# Sheet2.net
KiCad netlist of a schematic drawn in Altium Designer
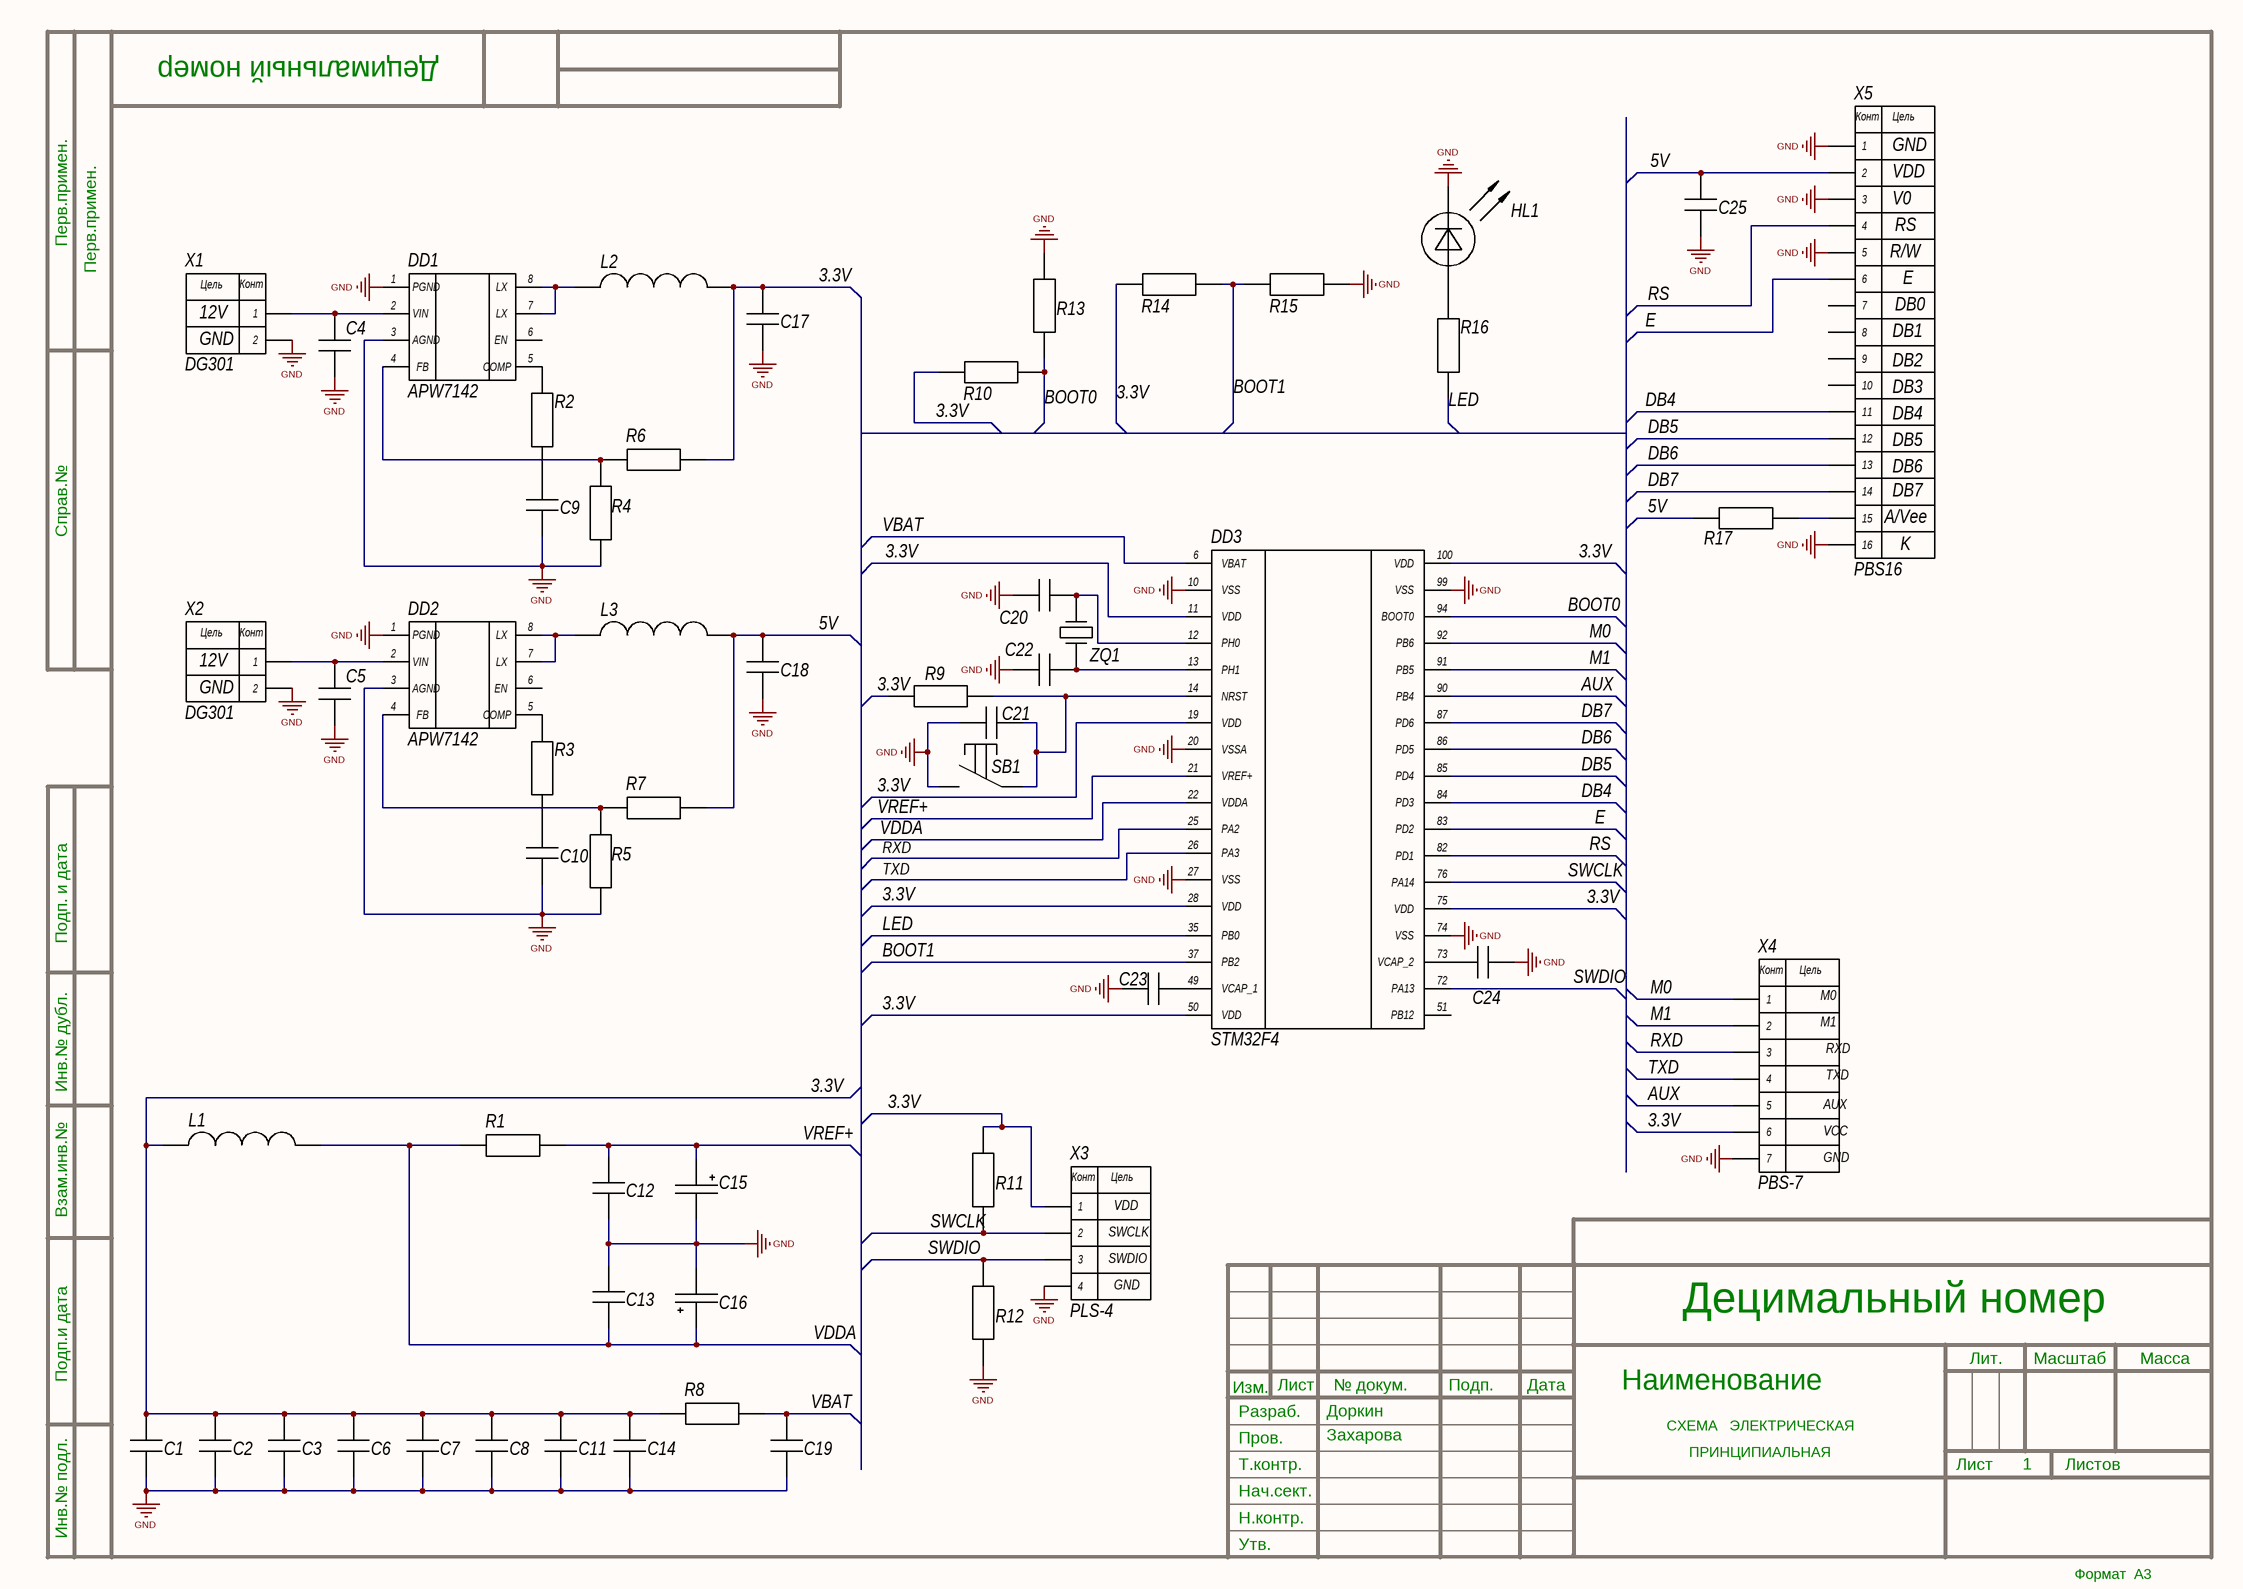
[diagram p0: Sheet2.SchDoc]

(export (version "E")
  (design (tool "Eeschema 10.0.6"))
  (components
    (comp (ref "C1") (value "100nF") (footprint "R1206") (libsource (lib "Schlib1") (part "C")))
    (comp (ref "C2") (value "C") (footprint "R1206") (libsource (lib "Schlib1") (part "C")))
    (comp (ref "C3") (value "C") (footprint "R1206") (libsource (lib "Schlib1") (part "C")))
    (comp (ref "C4") (value "2.2uF") (footprint "R1206") (libsource (lib "Schlib1") (part "C")))
    (comp (ref "C5") (value "2.2uF") (footprint "R1206") (libsource (lib "Schlib1") (part "C")))
    (comp (ref "C6") (value "C") (footprint "R1206") (libsource (lib "Schlib1") (part "C")))
    (comp (ref "C7") (value "C") (footprint "R1206") (libsource (lib "Schlib1") (part "C")))
    (comp (ref "C8") (value "C") (footprint "R1206") (libsource (lib "Schlib1") (part "C")))
    (comp (ref "C9") (value "1.5nF") (footprint "R1206") (libsource (lib "Schlib1") (part "C")))
    (comp (ref "C10") (value "1.5nF") (footprint "R1206") (libsource (lib "Schlib1") (part "C")))
    (comp (ref "C11") (value "C") (footprint "R1206") (libsource (lib "Schlib1") (part "C")))
    (comp (ref "C12") (value "1uF") (footprint "R1206") (libsource (lib "Schlib1") (part "C")))
    (comp (ref "C13") (value "1uF") (footprint "R1206") (libsource (lib "Schlib1") (part "C")))
    (comp (ref "C14") (value "C") (footprint "R1206") (libsource (lib "Schlib1") (part "C")))
    (comp (ref "C15") (value "100nF") (footprint "Rc3216") (libsource (lib "Schlib1") (part "C+")))
    (comp (ref "C16") (value "100nF") (footprint "Rc3216") (libsource (lib "Schlib1") (part "C+")))
    (comp (ref "C17") (value "22uF") (footprint "R1206") (libsource (lib "Schlib1") (part "C")))
    (comp (ref "C18") (value "22uF") (footprint "R1206") (libsource (lib "Schlib1") (part "C")))
    (comp (ref "C19") (value "1uF") (footprint "R1206") (libsource (lib "Schlib1") (part "C")))
    (comp (ref "C20") (value "20pF") (footprint "R1206") (libsource (lib "Schlib1") (part "C")))
    (comp (ref "C21") (value "100nF") (footprint "R1206") (libsource (lib "Schlib1") (part "C")))
    (comp (ref "C22") (value "20pF") (footprint "R1206") (libsource (lib "Schlib1") (part "C")))
    (comp (ref "C23") (value "2.2uF") (footprint "R1206") (libsource (lib "Schlib1") (part "C")))
    (comp (ref "C24") (value "2.2uF") (footprint "R1206") (libsource (lib "Schlib1") (part "C")))
    (comp (ref "C25") (value "100nF") (footprint "R1206") (libsource (lib "Schlib1") (part "C")))
    (comp (ref "DD1") (value "APW7142") (footprint "APW7142") (libsource (lib "Schlib1") (part "APW7142")))
    (comp (ref "DD2") (value "APW7142") (footprint "APW7142") (libsource (lib "Schlib1") (part "APW7142")))
    (comp (ref "DD3") (value "STM32F4") (footprint "STM32F4xx") (libsource (lib "Schlib1") (part "STM32F4")))
    (comp (ref "HL1") (value "Led") (footprint "LED") (libsource (lib "Schlib1") (part "Led")))
    (comp (ref "L1") (value "4.7uH") (footprint "R1206") (libsource (lib "Schlib1") (part "L")))
    (comp (ref "L2") (value "4.7uH") (footprint "R1206") (libsource (lib "Schlib1") (part "L")))
    (comp (ref "L3") (value "6.8uH") (footprint "R1206") (libsource (lib "Schlib1") (part "L")))
    (comp (ref "R1") (value "47") (footprint "R1206") (libsource (lib "Schlib1") (part "Res")))
    (comp (ref "R2") (value "10k") (footprint "R1206") (libsource (lib "Schlib1") (part "Res")))
    (comp (ref "R3") (value "10k") (footprint "R1206") (libsource (lib "Schlib1") (part "Res")))
    (comp (ref "R4") (value "15k") (footprint "R1206") (libsource (lib "Schlib1") (part "Res")))
    (comp (ref "R5") (value "12k") (footprint "R1206") (libsource (lib "Schlib1") (part "Res")))
    (comp (ref "R6") (value "46.9k") (footprint "R1206") (libsource (lib "Schlib1") (part "Res")))
    (comp (ref "R7") (value "63k") (footprint "R1206") (libsource (lib "Schlib1") (part "Res")))
    (comp (ref "R8") (value "10k") (footprint "R1206") (libsource (lib "Schlib1") (part "Res")))
    (comp (ref "R9") (value "100k") (footprint "R1206") (libsource (lib "Schlib1") (part "Res")))
    (comp (ref "R10") (value "100k") (footprint "R1206") (libsource (lib "Schlib1") (part "Res")))
    (comp (ref "R11") (value "10k") (footprint "R1206") (libsource (lib "Schlib1") (part "Res")))
    (comp (ref "R12") (value "10k") (footprint "R1206") (libsource (lib "Schlib1") (part "Res")))
    (comp (ref "R13") (value "510") (footprint "R1206") (libsource (lib "") (part "Res_1")))
    (comp (ref "R14") (value "10k") (footprint "R1206") (libsource (lib "Schlib1") (part "Res")))
    (comp (ref "R15") (value "510") (footprint "R1206") (libsource (lib "") (part "Res_1")))
    (comp (ref "R16") (value "Res") (footprint "R1206") (libsource (lib "Schlib1") (part "Res")))
    (comp (ref "R17") (value "100") (footprint "R1206") (libsource (lib "Schlib1") (part "Res")))
    (comp (ref "SB1") (value "BUTTON") (footprint "RESET_BUTTON") (libsource (lib "Schlib1") (part "BUTTON")))
    (comp (ref "X1") (value "DG301") (footprint "DG301") (libsource (lib "Schlib1") (part "DG301")))
    (comp (ref "X2") (value "DG301") (footprint "DG301") (libsource (lib "Schlib1") (part "DG301")))
    (comp (ref "X3") (value "PLS-4") (footprint "PLS4") (libsource (lib "Schlib1") (part "PLS-4")))
    (comp (ref "X4") (value "PBS-7") (footprint "PBS7") (libsource (lib "Schlib1") (part "PBS-7")))
    (comp (ref "X5") (value "PBS16") (footprint "PBS16") (libsource (lib "Schlib1") (part "Wh1602C")))
    (comp (ref "ZQ1") (value "KR") (footprint "HC-49SM") (libsource (lib "Schlib1") (part "KR")))
  )
  (nets
    (net (code "1") (name "/3.3V") (class "Default")
      (node (ref "C1") (pin "2") (pinfunction "2_2") (pintype "passive"))
      (node (ref "C11") (pin "2") (pinfunction "2_2") (pintype "passive"))
      (node (ref "C14") (pin "2") (pinfunction "2_2") (pintype "passive"))
      (node (ref "C17") (pin "1") (pinfunction "1_1") (pintype "passive"))
      (node (ref "C2") (pin "2") (pinfunction "2_2") (pintype "passive"))
      (node (ref "C3") (pin "2") (pinfunction "2_2") (pintype "passive"))
      (node (ref "C6") (pin "2") (pinfunction "2_2") (pintype "passive"))
      (node (ref "C7") (pin "2") (pinfunction "2_2") (pintype "passive"))
      (node (ref "C8") (pin "2") (pinfunction "2_2") (pintype "passive"))
      (node (ref "DD3") (pin "100") (pinfunction "VDD_100") (pintype "passive"))
      (node (ref "DD3") (pin "11") (pinfunction "VDD_11") (pintype "passive"))
      (node (ref "DD3") (pin "19") (pinfunction "VDD_19") (pintype "passive"))
      (node (ref "DD3") (pin "28") (pinfunction "VDD_28") (pintype "passive"))
      (node (ref "DD3") (pin "50") (pinfunction "VDD_50") (pintype "passive"))
      (node (ref "DD3") (pin "75") (pinfunction "VDD_75") (pintype "passive"))
      (node (ref "L1") (pin "1") (pinfunction "1_1") (pintype "passive"))
      (node (ref "L2") (pin "2") (pinfunction "2_2") (pintype "passive"))
      (node (ref "R10") (pin "2") (pinfunction "2_2") (pintype "passive"))
      (node (ref "R11") (pin "2") (pinfunction "2_2") (pintype "passive"))
      (node (ref "R14") (pin "1") (pinfunction "1_1") (pintype "passive"))
      (node (ref "R6") (pin "2") (pinfunction "2_2") (pintype "passive"))
      (node (ref "R8") (pin "1") (pinfunction "1_1") (pintype "passive"))
      (node (ref "R9") (pin "1") (pinfunction "1_1") (pintype "passive"))
      (node (ref "X3") (pin "1") (pinfunction "1_1") (pintype "passive"))
      (node (ref "X4") (pin "6") (pinfunction "6_6") (pintype "passive"))
    )
    (net (code "2") (name "/5V") (class "Default")
      (node (ref "C18") (pin "1") (pinfunction "1_1") (pintype "passive"))
      (node (ref "C25") (pin "2") (pinfunction "2_2") (pintype "passive"))
      (node (ref "L3") (pin "2") (pinfunction "2_2") (pintype "passive"))
      (node (ref "R17") (pin "1") (pinfunction "1_1") (pintype "passive"))
      (node (ref "R7") (pin "2") (pinfunction "2_2") (pintype "passive"))
      (node (ref "X5") (pin "2") (pinfunction "2_2") (pintype "passive"))
    )
    (net (code "3") (name "/AUX") (class "Default")
      (node (ref "DD3") (pin "90") (pinfunction "PB4_90") (pintype "passive"))
      (node (ref "X4") (pin "5") (pinfunction "5_5") (pintype "passive"))
    )
    (net (code "4") (name "/BOOT0") (class "Default")
      (node (ref "DD3") (pin "94") (pinfunction "BOOT0_94") (pintype "passive"))
      (node (ref "R10") (pin "1") (pinfunction "1_1") (pintype "passive"))
      (node (ref "R13") (pin "1") (pinfunction "1_1") (pintype "passive"))
    )
    (net (code "5") (name "/BOOT1") (class "Default")
      (node (ref "DD3") (pin "37") (pinfunction "PB2_37") (pintype "passive"))
      (node (ref "R14") (pin "2") (pinfunction "2_2") (pintype "passive"))
      (node (ref "R15") (pin "1") (pinfunction "1_1") (pintype "passive"))
    )
    (net (code "6") (name "/DB4") (class "Default")
      (node (ref "DD3") (pin "84") (pinfunction "PD3_84") (pintype "passive"))
      (node (ref "X5") (pin "11") (pinfunction "11_11") (pintype "passive"))
    )
    (net (code "7") (name "/DB5") (class "Default")
      (node (ref "DD3") (pin "85") (pinfunction "PD4_85") (pintype "passive"))
      (node (ref "X5") (pin "12") (pinfunction "12_12") (pintype "passive"))
    )
    (net (code "8") (name "/DB6") (class "Default")
      (node (ref "DD3") (pin "86") (pinfunction "PD5_86") (pintype "passive"))
      (node (ref "X5") (pin "13") (pinfunction "13_13") (pintype "passive"))
    )
    (net (code "9") (name "/DB7") (class "Default")
      (node (ref "DD3") (pin "87") (pinfunction "PD6_87") (pintype "passive"))
      (node (ref "X5") (pin "14") (pinfunction "14_14") (pintype "passive"))
    )
    (net (code "10") (name "/E") (class "Default")
      (node (ref "DD3") (pin "83") (pinfunction "PD2_83") (pintype "passive"))
      (node (ref "X5") (pin "18") (pinfunction "6_18") (pintype "passive"))
    )
    (net (code "11") (name "/LED") (class "Default")
      (node (ref "DD3") (pin "35") (pinfunction "PB0_35") (pintype "passive"))
      (node (ref "R16") (pin "1") (pinfunction "1_1") (pintype "passive"))
    )
    (net (code "12") (name "/M0") (class "Default")
      (node (ref "DD3") (pin "92") (pinfunction "PB6_92") (pintype "passive"))
      (node (ref "X4") (pin "1") (pinfunction "1_1") (pintype "passive"))
    )
    (net (code "13") (name "/M1") (class "Default")
      (node (ref "DD3") (pin "91") (pinfunction "PB5_91") (pintype "passive"))
      (node (ref "X4") (pin "2") (pinfunction "2_2") (pintype "passive"))
    )
    (net (code "14") (name "/RS") (class "Default")
      (node (ref "DD3") (pin "82") (pinfunction "PD1_82") (pintype "passive"))
      (node (ref "X5") (pin "4") (pinfunction "4_4") (pintype "passive"))
    )
    (net (code "15") (name "/RXD") (class "Default")
      (node (ref "DD3") (pin "25") (pinfunction "PA2_25") (pintype "passive"))
      (node (ref "X4") (pin "3") (pinfunction "3_3") (pintype "passive"))
    )
    (net (code "16") (name "/SWCLK") (class "Default")
      (node (ref "DD3") (pin "76") (pinfunction "PA14_76") (pintype "passive"))
      (node (ref "R11") (pin "1") (pinfunction "1_1") (pintype "passive"))
      (node (ref "X3") (pin "2") (pinfunction "2_2") (pintype "passive"))
    )
    (net (code "17") (name "/SWDIO") (class "Default")
      (node (ref "DD3") (pin "72") (pinfunction "PA13_72") (pintype "passive"))
      (node (ref "R12") (pin "2") (pinfunction "2_2") (pintype "passive"))
      (node (ref "X3") (pin "3") (pinfunction "3_3") (pintype "passive"))
    )
    (net (code "18") (name "/TXD") (class "Default")
      (node (ref "DD3") (pin "26") (pinfunction "PA3_26") (pintype "passive"))
      (node (ref "X4") (pin "4") (pinfunction "4_4") (pintype "passive"))
    )
    (net (code "19") (name "/VBAT") (class "Default")
      (node (ref "C19") (pin "2") (pinfunction "2_2") (pintype "passive"))
      (node (ref "DD3") (pin "6") (pinfunction "VBAT_6") (pintype "passive"))
      (node (ref "R8") (pin "2") (pinfunction "2_2") (pintype "passive"))
    )
    (net (code "20") (name "/VDDA") (class "Default")
      (node (ref "C13") (pin "1") (pinfunction "1_1") (pintype "passive"))
      (node (ref "C16") (pin "1") (pinfunction "1_1") (pintype "passive"))
      (node (ref "DD3") (pin "22") (pinfunction "VDDA_22") (pintype "passive"))
      (node (ref "L1") (pin "2") (pinfunction "2_2") (pintype "passive"))
      (node (ref "R1") (pin "1") (pinfunction "1_1") (pintype "passive"))
    )
    (net (code "21") (name "/VREF+") (class "Default")
      (node (ref "C12") (pin "2") (pinfunction "2_2") (pintype "passive"))
      (node (ref "C15") (pin "1") (pinfunction "1_1") (pintype "passive"))
      (node (ref "DD3") (pin "21") (pinfunction "VREF+_21") (pintype "passive"))
      (node (ref "R1") (pin "2") (pinfunction "2_2") (pintype "passive"))
    )
    (net (code "22") (name "GND") (class "Default")
      (node (ref "C1") (pin "1") (pinfunction "1_1") (pintype "passive"))
      (node (ref "C10") (pin "1") (pinfunction "1_1") (pintype "passive"))
      (node (ref "C11") (pin "1") (pinfunction "1_1") (pintype "passive"))
      (node (ref "C12") (pin "1") (pinfunction "1_1") (pintype "passive"))
      (node (ref "C13") (pin "2") (pinfunction "2_2") (pintype "passive"))
      (node (ref "C14") (pin "1") (pinfunction "1_1") (pintype "passive"))
      (node (ref "C15") (pin "2") (pinfunction "2_2") (pintype "passive"))
      (node (ref "C16") (pin "2") (pinfunction "2_2") (pintype "passive"))
      (node (ref "C17") (pin "2") (pinfunction "2_2") (pintype "passive"))
      (node (ref "C18") (pin "2") (pinfunction "2_2") (pintype "passive"))
      (node (ref "C19") (pin "1") (pinfunction "1_1") (pintype "passive"))
      (node (ref "C2") (pin "1") (pinfunction "1_1") (pintype "passive"))
      (node (ref "C20") (pin "1") (pinfunction "1_1") (pintype "passive"))
      (node (ref "C21") (pin "1") (pinfunction "1_1") (pintype "passive"))
      (node (ref "C22") (pin "1") (pinfunction "1_1") (pintype "passive"))
      (node (ref "C23") (pin "1") (pinfunction "1_1") (pintype "passive"))
      (node (ref "C24") (pin "1") (pinfunction "1_1") (pintype "passive"))
      (node (ref "C25") (pin "1") (pinfunction "1_1") (pintype "passive"))
      (node (ref "C3") (pin "1") (pinfunction "1_1") (pintype "passive"))
      (node (ref "C4") (pin "2") (pinfunction "2_2") (pintype "passive"))
      (node (ref "C5") (pin "2") (pinfunction "2_2") (pintype "passive"))
      (node (ref "C6") (pin "1") (pinfunction "1_1") (pintype "passive"))
      (node (ref "C7") (pin "1") (pinfunction "1_1") (pintype "passive"))
      (node (ref "C8") (pin "1") (pinfunction "1_1") (pintype "passive"))
      (node (ref "C9") (pin "1") (pinfunction "1_1") (pintype "passive"))
      (node (ref "DD1") (pin "1") (pinfunction "PGND_1") (pintype "passive"))
      (node (ref "DD1") (pin "3") (pinfunction "AGND_3") (pintype "passive"))
      (node (ref "DD2") (pin "1") (pinfunction "PGND_1") (pintype "passive"))
      (node (ref "DD2") (pin "3") (pinfunction "AGND_3") (pintype "passive"))
      (node (ref "DD3") (pin "10") (pinfunction "VSS_10") (pintype "passive"))
      (node (ref "DD3") (pin "20") (pinfunction "VSSA_20") (pintype "passive"))
      (node (ref "DD3") (pin "27") (pinfunction "VSS_27") (pintype "passive"))
      (node (ref "DD3") (pin "74") (pinfunction "VSS_74") (pintype "passive"))
      (node (ref "DD3") (pin "99") (pinfunction "VSS_99") (pintype "passive"))
      (node (ref "HL1") (pin "2") (pinfunction "2_2") (pintype "passive"))
      (node (ref "R12") (pin "1") (pinfunction "1_1") (pintype "passive"))
      (node (ref "R13") (pin "2") (pinfunction "2_2") (pintype "passive"))
      (node (ref "R15") (pin "2") (pinfunction "2_2") (pintype "passive"))
      (node (ref "R4") (pin "1") (pinfunction "1_1") (pintype "passive"))
      (node (ref "R5") (pin "1") (pinfunction "1_1") (pintype "passive"))
      (node (ref "SB1") (pin "2") (pinfunction "2_2") (pintype "passive"))
      (node (ref "X1") (pin "2") (pinfunction "2_2") (pintype "passive"))
      (node (ref "X2") (pin "2") (pinfunction "2_2") (pintype "passive"))
      (node (ref "X3") (pin "4") (pinfunction "4_4") (pintype "passive"))
      (node (ref "X4") (pin "7") (pinfunction "7_7") (pintype "passive"))
      (node (ref "X5") (pin "1") (pinfunction "1_1") (pintype "passive"))
      (node (ref "X5") (pin "16") (pinfunction "16_16") (pintype "passive"))
      (node (ref "X5") (pin "3") (pinfunction "3_3") (pintype "passive"))
      (node (ref "X5") (pin "5") (pinfunction "5_5") (pintype "passive"))
    )
    (net (code "23") (name "Net-(C9-Pad2)") (class "Default")
      (node (ref "C9") (pin "2") (pinfunction "2_2") (pintype "passive"))
      (node (ref "R2") (pin "1") (pinfunction "1_1") (pintype "passive"))
    )
    (net (code "24") (name "Net-(C10-Pad2)") (class "Default")
      (node (ref "C10") (pin "2") (pinfunction "2_2") (pintype "passive"))
      (node (ref "R3") (pin "1") (pinfunction "1_1") (pintype "passive"))
    )
    (net (code "25") (name "Net-(DD1-COMP)") (class "Default")
      (node (ref "DD1") (pin "5") (pinfunction "COMP_5") (pintype "passive"))
      (node (ref "R2") (pin "2") (pinfunction "2_2") (pintype "passive"))
    )
    (net (code "26") (name "Net-(DD1-FB)") (class "Default")
      (node (ref "DD1") (pin "4") (pinfunction "FB_4") (pintype "passive"))
      (node (ref "R4") (pin "2") (pinfunction "2_2") (pintype "passive"))
      (node (ref "R6") (pin "1") (pinfunction "1_1") (pintype "passive"))
    )
    (net (code "27") (name "Net-(DD1-LX-Pad7)") (class "Default")
      (node (ref "DD1") (pin "7") (pinfunction "LX_7") (pintype "passive"))
      (node (ref "DD1") (pin "8") (pinfunction "LX_8") (pintype "passive"))
      (node (ref "L2") (pin "1") (pinfunction "1_1") (pintype "passive"))
    )
    (net (code "28") (name "Net-(DD1-VIN)") (class "Default")
      (node (ref "C4") (pin "1") (pinfunction "1_1") (pintype "passive"))
      (node (ref "DD1") (pin "2") (pinfunction "VIN_2") (pintype "passive"))
      (node (ref "X1") (pin "1") (pinfunction "1_1") (pintype "passive"))
    )
    (net (code "29") (name "Net-(DD2-COMP)") (class "Default")
      (node (ref "DD2") (pin "5") (pinfunction "COMP_5") (pintype "passive"))
      (node (ref "R3") (pin "2") (pinfunction "2_2") (pintype "passive"))
    )
    (net (code "30") (name "Net-(DD2-FB)") (class "Default")
      (node (ref "DD2") (pin "4") (pinfunction "FB_4") (pintype "passive"))
      (node (ref "R5") (pin "2") (pinfunction "2_2") (pintype "passive"))
      (node (ref "R7") (pin "1") (pinfunction "1_1") (pintype "passive"))
    )
    (net (code "31") (name "Net-(DD2-LX-Pad7)") (class "Default")
      (node (ref "DD2") (pin "7") (pinfunction "LX_7") (pintype "passive"))
      (node (ref "DD2") (pin "8") (pinfunction "LX_8") (pintype "passive"))
      (node (ref "L3") (pin "1") (pinfunction "1_1") (pintype "passive"))
    )
    (net (code "32") (name "Net-(DD2-VIN)") (class "Default")
      (node (ref "C5") (pin "1") (pinfunction "1_1") (pintype "passive"))
      (node (ref "DD2") (pin "2") (pinfunction "VIN_2") (pintype "passive"))
      (node (ref "X2") (pin "1") (pinfunction "1_1") (pintype "passive"))
    )
    (net (code "33") (name "Net-(DD3-NRST)") (class "Default")
      (node (ref "C21") (pin "2") (pinfunction "2_2") (pintype "passive"))
      (node (ref "DD3") (pin "14") (pinfunction "NRST_14") (pintype "passive"))
      (node (ref "R9") (pin "2") (pinfunction "2_2") (pintype "passive"))
      (node (ref "SB1") (pin "1") (pinfunction "1_1") (pintype "passive"))
    )
    (net (code "34") (name "Net-(DD3-PH0)") (class "Default")
      (node (ref "C20") (pin "2") (pinfunction "2_2") (pintype "passive"))
      (node (ref "DD3") (pin "12") (pinfunction "PH0_12") (pintype "passive"))
      (node (ref "ZQ1") (pin "2") (pinfunction "2_2") (pintype "passive"))
    )
    (net (code "35") (name "Net-(DD3-PH1)") (class "Default")
      (node (ref "C22") (pin "2") (pinfunction "2_2") (pintype "passive"))
      (node (ref "DD3") (pin "13") (pinfunction "PH1_13") (pintype "passive"))
      (node (ref "ZQ1") (pin "1") (pinfunction "1_1") (pintype "passive"))
    )
    (net (code "36") (name "Net-(DD3-VCAP_1)") (class "Default")
      (node (ref "C23") (pin "2") (pinfunction "2_2") (pintype "passive"))
      (node (ref "DD3") (pin "49") (pinfunction "VCAP_1_49") (pintype "passive"))
    )
    (net (code "37") (name "Net-(DD3-VCAP_2)") (class "Default")
      (node (ref "C24") (pin "2") (pinfunction "2_2") (pintype "passive"))
      (node (ref "DD3") (pin "73") (pinfunction "VCAP_2_73") (pintype "passive"))
    )
    (net (code "38") (name "Net-(HL1-Pad1)") (class "Default")
      (node (ref "HL1") (pin "1") (pinfunction "1_1") (pintype "passive"))
      (node (ref "R16") (pin "2") (pinfunction "2_2") (pintype "passive"))
    )
    (net (code "39") (name "Net-(R17-Pad2)") (class "Default")
      (node (ref "R17") (pin "2") (pinfunction "2_2") (pintype "passive"))
      (node (ref "X5") (pin "15") (pinfunction "15_15") (pintype "passive"))
    )
    (net (code "40") (name "unconnected-(DD1-EN-Pad6)") (class "Default")
      (node (ref "DD1") (pin "6") (pinfunction "EN_6") (pintype "passive"))
    )
    (net (code "41") (name "unconnected-(DD2-EN-Pad6)") (class "Default")
      (node (ref "DD2") (pin "6") (pinfunction "EN_6") (pintype "passive"))
    )
    (net (code "42") (name "unconnected-(DD3-PB12-Pad51)") (class "Default")
      (node (ref "DD3") (pin "51") (pinfunction "PB12_51") (pintype "passive"))
    )
    (net (code "43") (name "unconnected-(X5-Pad7)") (class "Default")
      (node (ref "X5") (pin "7") (pinfunction "7_7") (pintype "passive"))
    )
    (net (code "44") (name "unconnected-(X5-Pad8)") (class "Default")
      (node (ref "X5") (pin "8") (pinfunction "8_8") (pintype "passive"))
    )
    (net (code "45") (name "unconnected-(X5-Pad9)") (class "Default")
      (node (ref "X5") (pin "9") (pinfunction "9_9") (pintype "passive"))
    )
    (net (code "46") (name "unconnected-(X5-Pad10)") (class "Default")
      (node (ref "X5") (pin "10") (pinfunction "10_10") (pintype "passive"))
    )
  )
)
